# design.net
KiCad netlist of a schematic drawn in Altium Designer
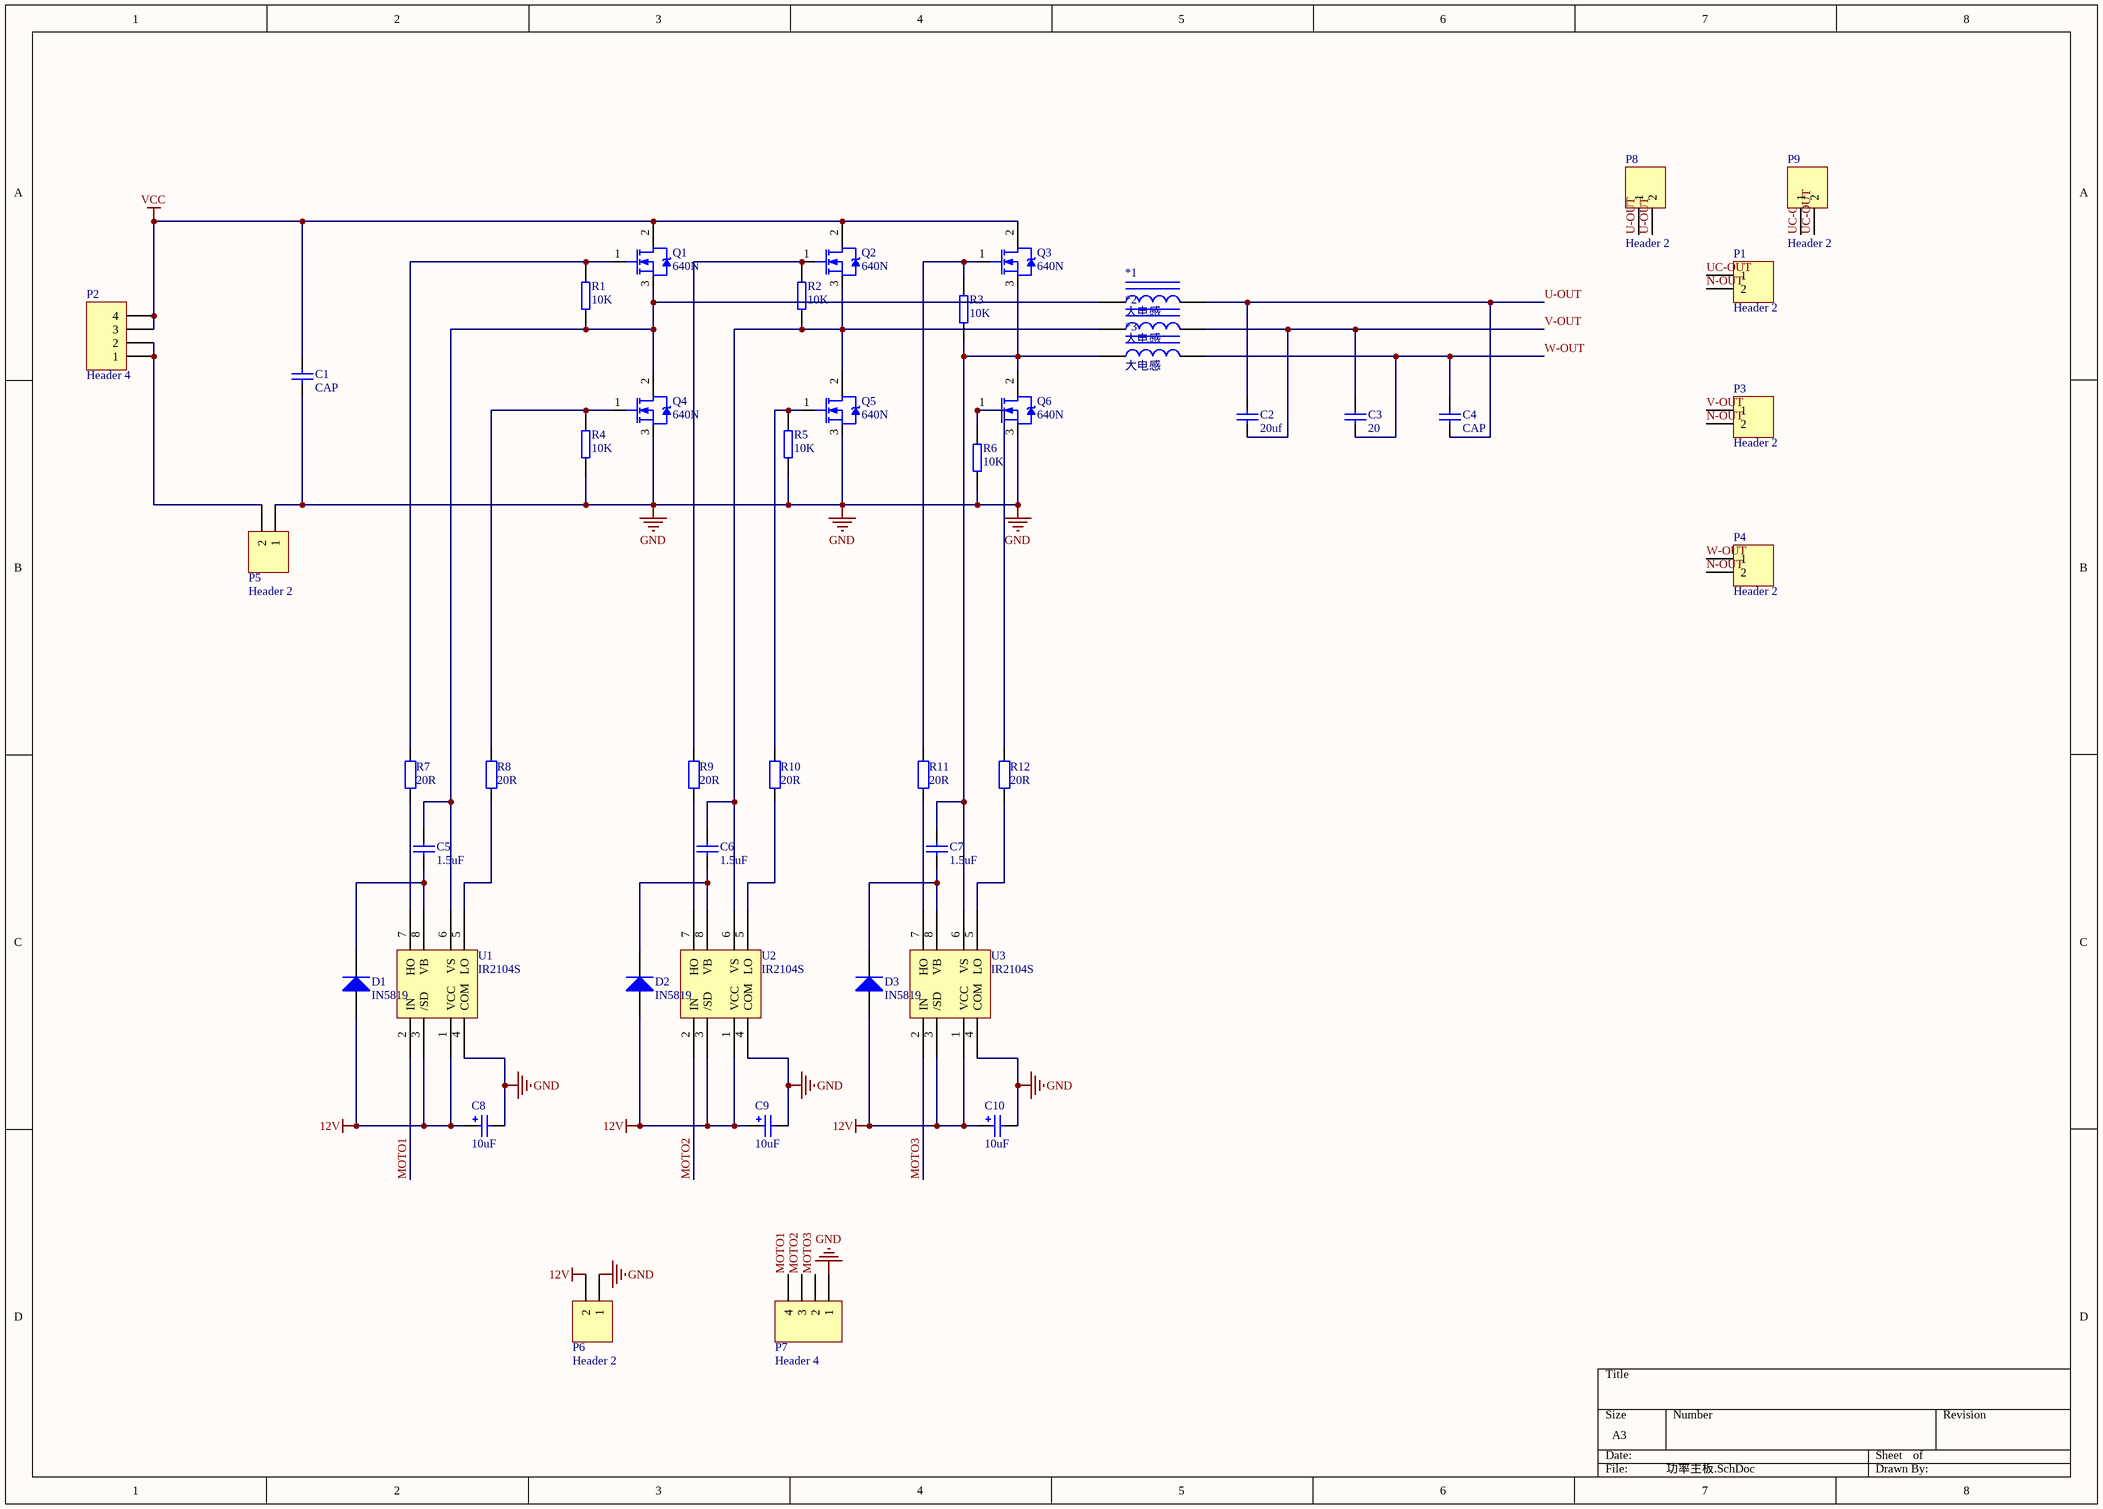
[diagram p0: 功率主板.SchDoc]

(export (version "E")
  (design (tool "Eeschema 10.0.6"))
  (components
    (comp (ref "*1") (value "大电感") (footprint "tie-in") (libsource (lib "自建库") (part "大电感")))
    (comp (ref "*2") (value "大电感") (footprint "tie-in") (libsource (lib "自建库") (part "大电感")))
    (comp (ref "*3") (value "大电感") (footprint "tie-in") (libsource (lib "自建库") (part "大电感")))
    (comp (ref "C1") (value "CAP") (footprint "RB7.6-15") (libsource (lib "自建库") (part "CAP")))
    (comp (ref "C2") (value "20uf") (footprint "20uF400V") (libsource (lib "自建库") (part "CAP")))
    (comp (ref "C3") (value "20") (footprint "20uF400V") (libsource (lib "自建库") (part "CAP")))
    (comp (ref "C4") (value "CAP") (footprint "20uF400V") (libsource (lib "自建库") (part "CAP")))
    (comp (ref "C5")
      (value "1.5uF")
      (footprint "接口2")
      (description "Capacitor (Semiconductor SIM Model)")
      (fields (field (name "Comment") "Cap Semi") (field (name "PUBLISHER") "Altium Limited"))
      (libsource (lib "Miscellaneous Devices") (part "Cap Semi"))
    )
    (comp (ref "C6")
      (value "1.5uF")
      (footprint "接口2")
      (description "Capacitor (Semiconductor SIM Model)")
      (fields (field (name "Comment") "Cap Semi") (field (name "PUBLISHER") "Altium Limited"))
      (libsource (lib "Miscellaneous Devices") (part "Cap Semi"))
    )
    (comp (ref "C7")
      (value "1.5uF")
      (footprint "接口2")
      (description "Capacitor (Semiconductor SIM Model)")
      (fields (field (name "Comment") "Cap Semi") (field (name "PUBLISHER") "Altium Limited"))
      (libsource (lib "Miscellaneous Devices") (part "Cap Semi"))
    )
    (comp (ref "C8")
      (value "10uF")
      (footprint "接口2")
      (description "Polarized Capacitor (Radial)")
      (fields (field (name "Comment") "Cap Pol1") (field (name "PUBLISHER") "Altium Limited"))
      (libsource (lib "MOS motor driving module ") (part "Cap Pol1"))
    )
    (comp (ref "C9")
      (value "10uF")
      (footprint "接口2")
      (description "Polarized Capacitor (Radial)")
      (fields (field (name "Comment") "Cap Pol1") (field (name "PUBLISHER") "Altium Limited"))
      (libsource (lib "MOS motor driving module ") (part "Cap Pol1"))
    )
    (comp (ref "C10")
      (value "10uF")
      (footprint "接口2")
      (description "Polarized Capacitor (Radial)")
      (fields (field (name "Comment") "Cap Pol1") (field (name "PUBLISHER") "Altium Limited"))
      (libsource (lib "MOS motor driving module ") (part "Cap Pol1"))
    )
    (comp (ref "D1")
      (value "IN5819")
      (footprint "DIO7.1-3.9x1.9")
      (description "Default Diode")
      (libsource (lib "MOS motor driving module ") (part "Diode"))
    )
    (comp (ref "D2")
      (value "IN5819")
      (footprint "DIO7.1-3.9x1.9")
      (description "Default Diode")
      (libsource (lib "MOS motor driving module ") (part "Diode"))
    )
    (comp (ref "D3")
      (value "IN5819")
      (footprint "DIO7.1-3.9x1.9")
      (description "Default Diode")
      (libsource (lib "MOS motor driving module ") (part "Diode"))
    )
    (comp (ref "P1")
      (value "Header 2")
      (footprint "tie-in")
      (description "Header, 2-Pin")
      (fields (field (name "PUBLISHER") "Altium Limited"))
      (libsource (lib "") (part "Header 2_2"))
    )
    (comp (ref "P2")
      (value "Header 4")
      (footprint "BIG_HEAD4")
      (description "Header, 4-Pin")
      (fields (field (name "PUBLISHER") "Altium Limited"))
      (libsource (lib "Miscellaneous Connectors") (part "Header 4"))
    )
    (comp (ref "P3")
      (value "Header 2")
      (footprint "tie-in")
      (description "Header, 2-Pin")
      (fields (field (name "PUBLISHER") "Altium Limited"))
      (libsource (lib "") (part "Header 2_2"))
    )
    (comp (ref "P4")
      (value "Header 2")
      (footprint "tie-in")
      (description "Header, 2-Pin")
      (fields (field (name "PUBLISHER") "Altium Limited"))
      (libsource (lib "") (part "Header 2_2"))
    )
    (comp (ref "P5")
      (value "Header 2")
      (footprint "tie-in")
      (description "Header, 2-Pin")
      (fields (field (name "PUBLISHER") "Altium Limited"))
      (libsource (lib "") (part "Header 2_1"))
    )
    (comp (ref "P6")
      (value "Header 2")
      (footprint "tie-in")
      (description "Header, 2-Pin")
      (fields (field (name "PUBLISHER") "Altium Limited"))
      (libsource (lib "") (part "Header 2_1"))
    )
    (comp (ref "P7")
      (value "Header 4")
      (footprint "BIG_HEAD4")
      (description "Header, 4-Pin")
      (fields (field (name "PUBLISHER") "Altium Limited"))
      (libsource (lib "") (part "Header 4_1"))
    )
    (comp (ref "P8")
      (value "Header 2")
      (footprint "tie-in")
      (description "Header, 2-Pin")
      (fields (field (name "PUBLISHER") "Altium Limited"))
      (libsource (lib "Miscellaneous Connectors") (part "Header 2"))
    )
    (comp (ref "P9")
      (value "Header 2")
      (footprint "tie-in")
      (description "Header, 2-Pin")
      (fields (field (name "PUBLISHER") "Altium Limited"))
      (libsource (lib "Miscellaneous Connectors") (part "Header 2"))
    )
    (comp (ref "Q1")
      (value "640N")
      (footprint "SFM-T3/A4.7V")
      (description "N-Channel Power MOSFET")
      (fields (field (name "PUBLISHER") "Altium Limited"))
      (libsource (lib "MOS motor driving module ") (part "NMOS-2"))
    )
    (comp (ref "Q2")
      (value "640N")
      (footprint "SFM-T3/A4.7V")
      (description "N-Channel Power MOSFET")
      (fields (field (name "PUBLISHER") "Altium Limited"))
      (libsource (lib "MOS motor driving module ") (part "NMOS-2"))
    )
    (comp (ref "Q3")
      (value "640N")
      (footprint "SFM-T3/A4.7V")
      (description "N-Channel Power MOSFET")
      (fields (field (name "PUBLISHER") "Altium Limited"))
      (libsource (lib "MOS motor driving module ") (part "NMOS-2"))
    )
    (comp (ref "Q4")
      (value "640N")
      (footprint "SFM-T3/A4.7V")
      (description "N-Channel Power MOSFET")
      (fields (field (name "PUBLISHER") "Altium Limited"))
      (libsource (lib "MOS motor driving module ") (part "NMOS-2"))
    )
    (comp (ref "Q5")
      (value "640N")
      (footprint "SFM-T3/A4.7V")
      (description "N-Channel Power MOSFET")
      (fields (field (name "PUBLISHER") "Altium Limited"))
      (libsource (lib "MOS motor driving module ") (part "NMOS-2"))
    )
    (comp (ref "Q6")
      (value "640N")
      (footprint "SFM-T3/A4.7V")
      (description "N-Channel Power MOSFET")
      (fields (field (name "PUBLISHER") "Altium Limited"))
      (libsource (lib "MOS motor driving module ") (part "NMOS-2"))
    )
    (comp (ref "R1") (value "10K") (footprint "RES") (libsource (lib "自建库") (part "res")))
    (comp (ref "R2") (value "10K") (footprint "RES") (libsource (lib "自建库") (part "res")))
    (comp (ref "R3") (value "10K") (footprint "RES") (libsource (lib "自建库") (part "res")))
    (comp (ref "R4") (value "10K") (footprint "RES") (libsource (lib "自建库") (part "res")))
    (comp (ref "R5") (value "10K") (footprint "RES") (libsource (lib "自建库") (part "res")))
    (comp (ref "R6") (value "10K") (footprint "RES") (libsource (lib "自建库") (part "res")))
    (comp (ref "R7")
      (value "20R")
      (footprint "RES")
      (description "Resistor")
      (fields (field (name "Comment") "Res2") (field (name "PUBLISHER") "Altium Limited"))
      (libsource (lib "MOS motor driving module ") (part "Res2"))
    )
    (comp (ref "R8")
      (value "20R")
      (footprint "RES")
      (description "Resistor")
      (fields (field (name "Comment") "Res2") (field (name "PUBLISHER") "Altium Limited"))
      (libsource (lib "MOS motor driving module ") (part "Res2"))
    )
    (comp (ref "R9")
      (value "20R")
      (footprint "RES")
      (description "Resistor")
      (fields (field (name "Comment") "Res2") (field (name "PUBLISHER") "Altium Limited"))
      (libsource (lib "MOS motor driving module ") (part "Res2"))
    )
    (comp (ref "R10")
      (value "20R")
      (footprint "RES")
      (description "Resistor")
      (fields (field (name "Comment") "Res2") (field (name "PUBLISHER") "Altium Limited"))
      (libsource (lib "MOS motor driving module ") (part "Res2"))
    )
    (comp (ref "R11")
      (value "20R")
      (footprint "RES")
      (description "Resistor")
      (fields (field (name "Comment") "Res2") (field (name "PUBLISHER") "Altium Limited"))
      (libsource (lib "MOS motor driving module ") (part "Res2"))
    )
    (comp (ref "R12")
      (value "20R")
      (footprint "RES")
      (description "Resistor")
      (fields (field (name "Comment") "Res2") (field (name "PUBLISHER") "Altium Limited"))
      (libsource (lib "MOS motor driving module ") (part "Res2"))
    )
    (comp (ref "U1")
      (value "IR2104S")
      (footprint "IR2104S")
      (libsource (lib "MOS motor driving module ") (part "Component_1_1"))
    )
    (comp (ref "U2")
      (value "IR2104S")
      (footprint "IR2104S")
      (libsource (lib "MOS motor driving module ") (part "Component_1_1"))
    )
    (comp (ref "U3")
      (value "IR2104S")
      (footprint "IR2104S")
      (libsource (lib "MOS motor driving module ") (part "Component_1_1"))
    )
  )
  (nets
    (net (code "1") (name "/MOTO1") (class "Default")
      (node (ref "P7") (pin "4") (pinfunction "4_4") (pintype "passive"))
      (node (ref "U1") (pin "2") (pinfunction "IN_2") (pintype "passive"))
    )
    (net (code "2") (name "/MOTO2") (class "Default")
      (node (ref "P7") (pin "3") (pinfunction "3_3") (pintype "passive"))
      (node (ref "U2") (pin "2") (pinfunction "IN_2") (pintype "passive"))
    )
    (net (code "3") (name "/MOTO3") (class "Default")
      (node (ref "P7") (pin "2") (pinfunction "2_2") (pintype "passive"))
      (node (ref "U3") (pin "2") (pinfunction "IN_2") (pintype "passive"))
    )
    (net (code "4") (name "/N-OUT") (class "Default")
      (node (ref "P1") (pin "2") (pinfunction "2_2") (pintype "passive"))
      (node (ref "P3") (pin "2") (pinfunction "2_2") (pintype "passive"))
      (node (ref "P4") (pin "2") (pinfunction "2_2") (pintype "passive"))
    )
    (net (code "5") (name "/U-OUT") (class "Default")
      (node (ref "*1") (pin "2") (pinfunction "2_2") (pintype "passive"))
      (node (ref "C2") (pin "2") (pinfunction "2_2") (pintype "passive"))
      (node (ref "C4") (pin "1") (pinfunction "1_1") (pintype "passive"))
      (node (ref "P8") (pin "1") (pinfunction "1_1") (pintype "passive"))
      (node (ref "P8") (pin "2") (pinfunction "2_2") (pintype "passive"))
    )
    (net (code "6") (name "/UC-OUT") (class "Default")
      (node (ref "P1") (pin "1") (pinfunction "1_1") (pintype "passive"))
      (node (ref "P9") (pin "1") (pinfunction "1_1") (pintype "passive"))
      (node (ref "P9") (pin "2") (pinfunction "2_2") (pintype "passive"))
    )
    (net (code "7") (name "/V-OUT") (class "Default")
      (node (ref "*2") (pin "2") (pinfunction "2_2") (pintype "passive"))
      (node (ref "C2") (pin "1") (pinfunction "1_1") (pintype "passive"))
      (node (ref "C3") (pin "2") (pinfunction "2_2") (pintype "passive"))
      (node (ref "P3") (pin "1") (pinfunction "1_1") (pintype "passive"))
    )
    (net (code "8") (name "/W-OUT") (class "Default")
      (node (ref "*3") (pin "2") (pinfunction "2_2") (pintype "passive"))
      (node (ref "C3") (pin "1") (pinfunction "1_1") (pintype "passive"))
      (node (ref "C4") (pin "2") (pinfunction "2_2") (pintype "passive"))
      (node (ref "P4") (pin "1") (pinfunction "1_1") (pintype "passive"))
    )
    (net (code "9") (name "12V") (class "Default")
      (node (ref "C10") (pin "1") (pinfunction "1_1") (pintype "passive"))
      (node (ref "C8") (pin "1") (pinfunction "1_1") (pintype "passive"))
      (node (ref "C9") (pin "1") (pinfunction "1_1") (pintype "passive"))
      (node (ref "D1") (pin "1") (pinfunction "A_1") (pintype "passive"))
      (node (ref "D2") (pin "1") (pinfunction "A_1") (pintype "passive"))
      (node (ref "D3") (pin "1") (pinfunction "A_1") (pintype "passive"))
      (node (ref "P6") (pin "2") (pinfunction "2_2") (pintype "passive"))
      (node (ref "U1") (pin "1") (pinfunction "VCC_1") (pintype "passive"))
      (node (ref "U1") (pin "3") (pinfunction "/SD_3") (pintype "passive"))
      (node (ref "U2") (pin "1") (pinfunction "VCC_1") (pintype "passive"))
      (node (ref "U2") (pin "3") (pinfunction "/SD_3") (pintype "passive"))
      (node (ref "U3") (pin "1") (pinfunction "VCC_1") (pintype "passive"))
      (node (ref "U3") (pin "3") (pinfunction "/SD_3") (pintype "passive"))
    )
    (net (code "10") (name "GND") (class "Default")
      (node (ref "C1") (pin "1") (pinfunction "1_1") (pintype "passive"))
      (node (ref "C10") (pin "2") (pinfunction "2_2") (pintype "passive"))
      (node (ref "C8") (pin "2") (pinfunction "2_2") (pintype "passive"))
      (node (ref "C9") (pin "2") (pinfunction "2_2") (pintype "passive"))
      (node (ref "P5") (pin "1") (pinfunction "1_1") (pintype "passive"))
      (node (ref "P6") (pin "1") (pinfunction "1_1") (pintype "passive"))
      (node (ref "P7") (pin "1") (pinfunction "1_1") (pintype "passive"))
      (node (ref "Q4") (pin "3") (pinfunction "S_3") (pintype "passive"))
      (node (ref "Q5") (pin "3") (pinfunction "S_3") (pintype "passive"))
      (node (ref "Q6") (pin "3") (pinfunction "S_3") (pintype "passive"))
      (node (ref "R4") (pin "1") (pinfunction "1_1") (pintype "passive"))
      (node (ref "R5") (pin "1") (pinfunction "1_1") (pintype "passive"))
      (node (ref "R6") (pin "1") (pinfunction "1_1") (pintype "passive"))
      (node (ref "U1") (pin "4") (pinfunction "COM_4") (pintype "passive"))
      (node (ref "U2") (pin "4") (pinfunction "COM_4") (pintype "passive"))
      (node (ref "U3") (pin "4") (pinfunction "COM_4") (pintype "passive"))
    )
    (net (code "11") (name "Net-(D1-K)") (class "Default")
      (node (ref "C5") (pin "2") (pinfunction "2_2") (pintype "passive"))
      (node (ref "D1") (pin "2") (pinfunction "K_2") (pintype "passive"))
      (node (ref "U1") (pin "8") (pinfunction "VB_8") (pintype "passive"))
    )
    (net (code "12") (name "Net-(D2-K)") (class "Default")
      (node (ref "C6") (pin "2") (pinfunction "2_2") (pintype "passive"))
      (node (ref "D2") (pin "2") (pinfunction "K_2") (pintype "passive"))
      (node (ref "U2") (pin "8") (pinfunction "VB_8") (pintype "passive"))
    )
    (net (code "13") (name "Net-(D3-K)") (class "Default")
      (node (ref "C7") (pin "2") (pinfunction "2_2") (pintype "passive"))
      (node (ref "D3") (pin "2") (pinfunction "K_2") (pintype "passive"))
      (node (ref "U3") (pin "8") (pinfunction "VB_8") (pintype "passive"))
    )
    (net (code "14") (name "Net-(P2-Pad1)") (class "Default")
      (node (ref "P2") (pin "1") (pinfunction "1_1") (pintype "passive"))
      (node (ref "P2") (pin "2") (pinfunction "2_2") (pintype "passive"))
      (node (ref "P5") (pin "2") (pinfunction "2_2") (pintype "passive"))
    )
    (net (code "15") (name "Net-(Q1-G)") (class "Default")
      (node (ref "Q1") (pin "1") (pinfunction "G_1") (pintype "passive"))
      (node (ref "R1") (pin "2") (pinfunction "2_2") (pintype "passive"))
      (node (ref "R7") (pin "2") (pinfunction "2_2") (pintype "passive"))
    )
    (net (code "16") (name "Net-(Q1-S)") (class "Default")
      (node (ref "*1") (pin "1") (pinfunction "1_1") (pintype "passive"))
      (node (ref "C5") (pin "1") (pinfunction "1_1") (pintype "passive"))
      (node (ref "Q1") (pin "3") (pinfunction "S_3") (pintype "passive"))
      (node (ref "Q4") (pin "2") (pinfunction "D_2") (pintype "passive"))
      (node (ref "R1") (pin "1") (pinfunction "1_1") (pintype "passive"))
      (node (ref "U1") (pin "6") (pinfunction "VS_6") (pintype "passive"))
    )
    (net (code "17") (name "Net-(Q2-G)") (class "Default")
      (node (ref "Q2") (pin "1") (pinfunction "G_1") (pintype "passive"))
      (node (ref "R2") (pin "2") (pinfunction "2_2") (pintype "passive"))
      (node (ref "R9") (pin "2") (pinfunction "2_2") (pintype "passive"))
    )
    (net (code "18") (name "Net-(Q2-S)") (class "Default")
      (node (ref "*2") (pin "1") (pinfunction "1_1") (pintype "passive"))
      (node (ref "C6") (pin "1") (pinfunction "1_1") (pintype "passive"))
      (node (ref "Q2") (pin "3") (pinfunction "S_3") (pintype "passive"))
      (node (ref "Q5") (pin "2") (pinfunction "D_2") (pintype "passive"))
      (node (ref "R2") (pin "1") (pinfunction "1_1") (pintype "passive"))
      (node (ref "U2") (pin "6") (pinfunction "VS_6") (pintype "passive"))
    )
    (net (code "19") (name "Net-(Q3-G)") (class "Default")
      (node (ref "Q3") (pin "1") (pinfunction "G_1") (pintype "passive"))
      (node (ref "R11") (pin "2") (pinfunction "2_2") (pintype "passive"))
      (node (ref "R3") (pin "2") (pinfunction "2_2") (pintype "passive"))
    )
    (net (code "20") (name "Net-(Q3-S)") (class "Default")
      (node (ref "*3") (pin "1") (pinfunction "1_1") (pintype "passive"))
      (node (ref "C7") (pin "1") (pinfunction "1_1") (pintype "passive"))
      (node (ref "Q3") (pin "3") (pinfunction "S_3") (pintype "passive"))
      (node (ref "Q6") (pin "2") (pinfunction "D_2") (pintype "passive"))
      (node (ref "R3") (pin "1") (pinfunction "1_1") (pintype "passive"))
      (node (ref "U3") (pin "6") (pinfunction "VS_6") (pintype "passive"))
    )
    (net (code "21") (name "Net-(Q4-G)") (class "Default")
      (node (ref "Q4") (pin "1") (pinfunction "G_1") (pintype "passive"))
      (node (ref "R4") (pin "2") (pinfunction "2_2") (pintype "passive"))
      (node (ref "R8") (pin "2") (pinfunction "2_2") (pintype "passive"))
    )
    (net (code "22") (name "Net-(Q5-G)") (class "Default")
      (node (ref "Q5") (pin "1") (pinfunction "G_1") (pintype "passive"))
      (node (ref "R10") (pin "2") (pinfunction "2_2") (pintype "passive"))
      (node (ref "R5") (pin "2") (pinfunction "2_2") (pintype "passive"))
    )
    (net (code "23") (name "Net-(Q6-G)") (class "Default")
      (node (ref "Q6") (pin "1") (pinfunction "G_1") (pintype "passive"))
      (node (ref "R12") (pin "2") (pinfunction "2_2") (pintype "passive"))
      (node (ref "R6") (pin "2") (pinfunction "2_2") (pintype "passive"))
    )
    (net (code "24") (name "Net-(U1-HO)") (class "Default")
      (node (ref "R7") (pin "1") (pinfunction "1_1") (pintype "passive"))
      (node (ref "U1") (pin "7") (pinfunction "HO_7") (pintype "passive"))
    )
    (net (code "25") (name "Net-(U1-LO)") (class "Default")
      (node (ref "R8") (pin "1") (pinfunction "1_1") (pintype "passive"))
      (node (ref "U1") (pin "5") (pinfunction "LO_5") (pintype "passive"))
    )
    (net (code "26") (name "Net-(U2-HO)") (class "Default")
      (node (ref "R9") (pin "1") (pinfunction "1_1") (pintype "passive"))
      (node (ref "U2") (pin "7") (pinfunction "HO_7") (pintype "passive"))
    )
    (net (code "27") (name "Net-(U2-LO)") (class "Default")
      (node (ref "R10") (pin "1") (pinfunction "1_1") (pintype "passive"))
      (node (ref "U2") (pin "5") (pinfunction "LO_5") (pintype "passive"))
    )
    (net (code "28") (name "Net-(U3-HO)") (class "Default")
      (node (ref "R11") (pin "1") (pinfunction "1_1") (pintype "passive"))
      (node (ref "U3") (pin "7") (pinfunction "HO_7") (pintype "passive"))
    )
    (net (code "29") (name "Net-(U3-LO)") (class "Default")
      (node (ref "R12") (pin "1") (pinfunction "1_1") (pintype "passive"))
      (node (ref "U3") (pin "5") (pinfunction "LO_5") (pintype "passive"))
    )
    (net (code "30") (name "VCC") (class "Default")
      (node (ref "C1") (pin "2") (pinfunction "2_2") (pintype "passive"))
      (node (ref "P2") (pin "3") (pinfunction "3_3") (pintype "passive"))
      (node (ref "P2") (pin "4") (pinfunction "4_4") (pintype "passive"))
      (node (ref "Q1") (pin "2") (pinfunction "D_2") (pintype "passive"))
      (node (ref "Q2") (pin "2") (pinfunction "D_2") (pintype "passive"))
      (node (ref "Q3") (pin "2") (pinfunction "D_2") (pintype "passive"))
    )
  )
)
